# node.net
KiCad netlist of a schematic drawn in EAGLE
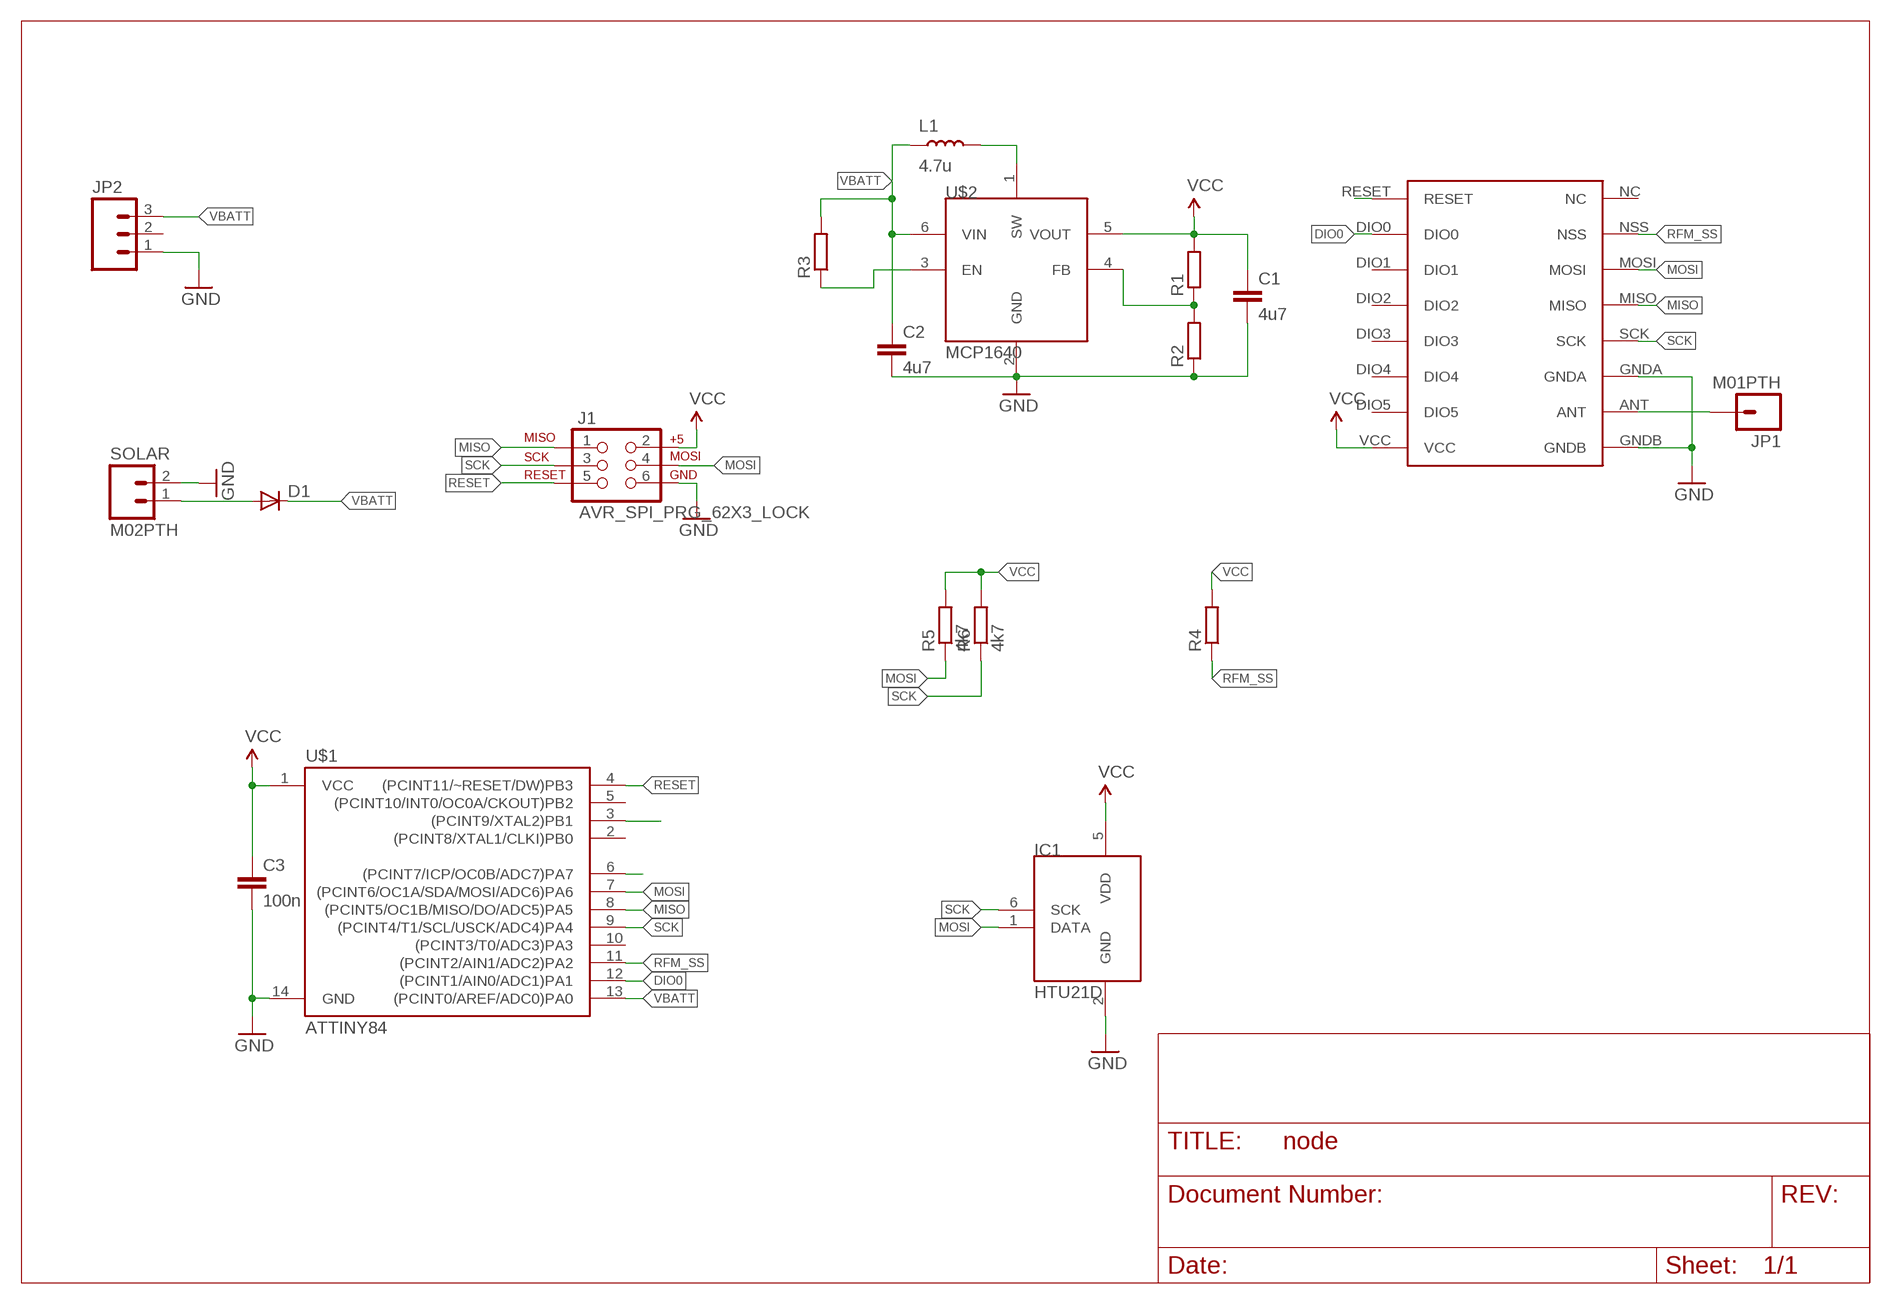
[diagram p0: schematic, sheet 1]

(export (version "E")
  (design (tool "Eeschema 10.0.6"))
  (components
    (comp (ref "C1")
      (value "4u7")
      (footprint "eagle-import:C0603")
      (libsource (lib "eagle-import") (part "C-EUC0603"))
    )
    (comp (ref "C2")
      (value "4u7")
      (footprint "eagle-import:C0603")
      (libsource (lib "eagle-import") (part "C-EUC0603"))
    )
    (comp (ref "C3")
      (value "100n")
      (footprint "eagle-import:C0603")
      (libsource (lib "eagle-import") (part "C-EUC0603"))
    )
    (comp (ref "D1")
      (value "DIODE-SOD123")
      (footprint "eagle-import:SOD123")
      (libsource (lib "eagle-import") (part "DIODE-SOD123"))
    )
    (comp (ref "IC1")
      (value "HTU21D")
      (footprint "eagle-import:DFN6-L")
      (libsource (lib "eagle-import") (part "HTU21D"))
    )
    (comp (ref "J1")
      (value "AVR_SPI_PRG_62X3_LOCK")
      (footprint "eagle-import:2X3_LOCK")
      (libsource (lib "eagle-import") (part "AVR_SPI_PRG_62X3_LOCK"))
    )
    (comp (ref "JP1")
      (value "M01PTH")
      (footprint "eagle-import:1X01")
      (libsource (lib "eagle-import") (part "M01PTH"))
    )
    (comp (ref "JP2")
      (value "M03PTH")
      (footprint "eagle-import:1X03")
      (libsource (lib "eagle-import") (part "M03PTH"))
    )
    (comp (ref "L1")
      (value "4.7u")
      (footprint "eagle-import:L0603-N")
      (libsource (lib "eagle-import") (part "INDUCTOR0603-N"))
    )
    (comp (ref "R1")
      (value "R-EU_R0603")
      (footprint "eagle-import:R0603")
      (libsource (lib "eagle-import") (part "R-EU_R0603"))
    )
    (comp (ref "R2")
      (value "R-EU_R0603")
      (footprint "eagle-import:R0603")
      (libsource (lib "eagle-import") (part "R-EU_R0603"))
    )
    (comp (ref "R3")
      (value "R-EU_R0603")
      (footprint "eagle-import:R0603")
      (libsource (lib "eagle-import") (part "R-EU_R0603"))
    )
    (comp (ref "R4")
      (value "R-EU_R0603")
      (footprint "eagle-import:R0603")
      (libsource (lib "eagle-import") (part "R-EU_R0603"))
    )
    (comp (ref "R5")
      (value "4k7")
      (footprint "eagle-import:R0603")
      (libsource (lib "eagle-import") (part "R-EU_R0603"))
    )
    (comp (ref "R6")
      (value "4k7")
      (footprint "eagle-import:R0603")
      (libsource (lib "eagle-import") (part "R-EU_R0603"))
    )
    (comp (ref "SOLAR")
      (value "M02PTH")
      (footprint "eagle-import:1X02")
      (libsource (lib "eagle-import") (part "M02PTH"))
    )
    (comp (ref "U$1")
      (value "ATTINY84")
      (footprint "eagle-import:SO14")
      (libsource (lib "eagle-import") (part "ATTINY84"))
    )
    (comp (ref "U$2")
      (value "MCP1640")
      (footprint "eagle-import:SOT23-6")
      (libsource (lib "eagle-import") (part "MCP1640"))
    )
    (comp (ref "U$4")
      (value "RFM69HW")
      (footprint "eagle-import:RFM")
      (libsource (lib "eagle-import") (part "RFM69HW"))
    )
  )
  (nets
    (net (code "1") (name "DIO0") (class "Default")
      (node (ref "U$1") (pin "12") (pinfunction "(PCINT1/AIN0/ADC1)PA1_12") (pintype "bidirectional"))
      (node (ref "U$4") (pin "DIO0") (pinfunction "DIO0_DIO0") (pintype "bidirectional"))
    )
    (net (code "2") (name "GND") (class "Default")
      (node (ref "C1") (pin "2") (pinfunction "2_2") (pintype "passive"))
      (node (ref "C2") (pin "2") (pinfunction "2_2") (pintype "passive"))
      (node (ref "C3") (pin "2") (pinfunction "2_2") (pintype "passive"))
      (node (ref "IC1") (pin "2") (pinfunction "GND_2") (pintype "power_in"))
      (node (ref "J1") (pin "6") (pinfunction "6_6") (pintype "passive"))
      (node (ref "JP2") (pin "1") (pinfunction "1_1") (pintype "passive"))
      (node (ref "R2") (pin "1") (pinfunction "1_1") (pintype "passive"))
      (node (ref "SOLAR") (pin "2") (pinfunction "2_2") (pintype "passive"))
      (node (ref "U$1") (pin "14") (pinfunction "GND_14") (pintype "bidirectional"))
      (node (ref "U$2") (pin "2") (pinfunction "GND_2") (pintype "power_in"))
      (node (ref "U$4") (pin "GNDA") (pinfunction "GNDA_GNDA") (pintype "bidirectional"))
      (node (ref "U$4") (pin "GNDB") (pinfunction "GNDB_GNDB") (pintype "bidirectional"))
    )
    (net (code "3") (name "MISO") (class "Default")
      (node (ref "J1") (pin "1") (pinfunction "1_1") (pintype "passive"))
      (node (ref "U$1") (pin "8") (pinfunction "(PCINT5/OC1B/MISO/DO/ADC5)PA5_8") (pintype "bidirectional"))
      (node (ref "U$4") (pin "MISO") (pinfunction "MISO_MISO") (pintype "bidirectional"))
    )
    (net (code "4") (name "MOSI") (class "Default")
      (node (ref "IC1") (pin "1") (pinfunction "DATA_1") (pintype "bidirectional"))
      (node (ref "J1") (pin "4") (pinfunction "4_4") (pintype "passive"))
      (node (ref "R5") (pin "1") (pinfunction "1_1") (pintype "passive"))
      (node (ref "U$1") (pin "7") (pinfunction "(PCINT6/OC1A/SDA/MOSI/ADC6)PA6_7") (pintype "bidirectional"))
      (node (ref "U$4") (pin "MOSI") (pinfunction "MOSI_MOSI") (pintype "bidirectional"))
    )
    (net (code "5") (name "Net-(D1-PadA)") (class "Default")
      (node (ref "D1") (pin "A") (pinfunction "A_A") (pintype "passive"))
      (node (ref "SOLAR") (pin "1") (pinfunction "1_1") (pintype "passive"))
    )
    (net (code "6") (name "Net-(JP1-Pad1)") (class "Default")
      (node (ref "JP1") (pin "1") (pinfunction "1_1") (pintype "passive"))
      (node (ref "U$4") (pin "ANT") (pinfunction "ANT_ANT") (pintype "bidirectional"))
    )
    (net (code "7") (name "Net-(L1-P$2)") (class "Default")
      (node (ref "L1") (pin "2") (pinfunction "P$2_2") (pintype "passive"))
      (node (ref "U$2") (pin "1") (pinfunction "SW_1") (pintype "input"))
    )
    (net (code "8") (name "Net-(U$2-EN)") (class "Default")
      (node (ref "R3") (pin "1") (pinfunction "1_1") (pintype "passive"))
      (node (ref "U$2") (pin "3") (pinfunction "EN_3") (pintype "input"))
    )
    (net (code "9") (name "Net-(U$2-FB)") (class "Default")
      (node (ref "R1") (pin "1") (pinfunction "1_1") (pintype "passive"))
      (node (ref "R2") (pin "2") (pinfunction "2_2") (pintype "passive"))
      (node (ref "U$2") (pin "4") (pinfunction "FB_4") (pintype "input"))
    )
    (net (code "10") (name "RESET") (class "Default")
      (node (ref "J1") (pin "5") (pinfunction "5_5") (pintype "passive"))
      (node (ref "U$1") (pin "4") (pinfunction "(PCINT11/~{RESET/DW})PB3_4") (pintype "bidirectional"))
    )
    (net (code "11") (name "RFM_SS") (class "Default")
      (node (ref "R4") (pin "1") (pinfunction "1_1") (pintype "passive"))
      (node (ref "U$1") (pin "11") (pinfunction "(PCINT2/AIN1/ADC2)PA2_11") (pintype "bidirectional"))
      (node (ref "U$4") (pin "NSS") (pinfunction "NSS_NSS") (pintype "bidirectional"))
    )
    (net (code "12") (name "SCK") (class "Default")
      (node (ref "IC1") (pin "6") (pinfunction "SCK_6") (pintype "input"))
      (node (ref "J1") (pin "3") (pinfunction "3_3") (pintype "passive"))
      (node (ref "R6") (pin "1") (pinfunction "1_1") (pintype "passive"))
      (node (ref "U$1") (pin "9") (pinfunction "(PCINT4/T1/SCL/USCK/ADC4)PA4_9") (pintype "bidirectional"))
      (node (ref "U$4") (pin "SCK") (pinfunction "SCK_SCK") (pintype "bidirectional"))
    )
    (net (code "13") (name "VBATT") (class "Default")
      (node (ref "C2") (pin "1") (pinfunction "1_1") (pintype "passive"))
      (node (ref "D1") (pin "C") (pinfunction "C_C") (pintype "passive"))
      (node (ref "JP2") (pin "3") (pinfunction "3_3") (pintype "passive"))
      (node (ref "L1") (pin "1") (pinfunction "P$1_1") (pintype "passive"))
      (node (ref "R3") (pin "2") (pinfunction "2_2") (pintype "passive"))
      (node (ref "U$1") (pin "13") (pinfunction "(PCINT0/AREF/ADC0)PA0_13") (pintype "bidirectional"))
      (node (ref "U$2") (pin "6") (pinfunction "VIN_6") (pintype "power_in"))
    )
    (net (code "14") (name "VCC") (class "Default")
      (node (ref "C1") (pin "1") (pinfunction "1_1") (pintype "passive"))
      (node (ref "C3") (pin "1") (pinfunction "1_1") (pintype "passive"))
      (node (ref "IC1") (pin "5") (pinfunction "VDD_5") (pintype "power_in"))
      (node (ref "J1") (pin "2") (pinfunction "2_2") (pintype "passive"))
      (node (ref "R1") (pin "2") (pinfunction "2_2") (pintype "passive"))
      (node (ref "R4") (pin "2") (pinfunction "2_2") (pintype "passive"))
      (node (ref "R5") (pin "2") (pinfunction "2_2") (pintype "passive"))
      (node (ref "R6") (pin "2") (pinfunction "2_2") (pintype "passive"))
      (node (ref "U$1") (pin "1") (pinfunction "VCC_1") (pintype "bidirectional"))
      (node (ref "U$2") (pin "5") (pinfunction "VOUT_5") (pintype "output"))
      (node (ref "U$4") (pin "VCC") (pinfunction "VCC_VCC") (pintype "bidirectional"))
    )
    (net (code "15") (name "unconnected-(JP2-Pad2)") (class "Default")
      (node (ref "JP2") (pin "2") (pinfunction "2_2") (pintype "passive"))
    )
    (net (code "16") (name "unconnected-(U$1-(PCINT3{slash}T0{slash}ADC3)PA3-Pad10)") (class "Default")
      (node (ref "U$1") (pin "10") (pinfunction "(PCINT3/T0/ADC3)PA3_10") (pintype "bidirectional"))
    )
    (net (code "17") (name "unconnected-(U$1-(PCINT7{slash}ICP{slash}OC0B{slash}ADC7)PA7-Pad6)") (class "Default")
      (node (ref "U$1") (pin "6") (pinfunction "(PCINT7/ICP/OC0B/ADC7)PA7_6") (pintype "bidirectional"))
    )
    (net (code "18") (name "unconnected-(U$1-(PCINT8{slash}XTAL1{slash}CLKI)PB0-Pad2)") (class "Default")
      (node (ref "U$1") (pin "2") (pinfunction "(PCINT8/XTAL1/CLKI)PB0_2") (pintype "bidirectional"))
    )
    (net (code "19") (name "unconnected-(U$1-(PCINT9{slash}XTAL2)PB1-Pad3)") (class "Default")
      (node (ref "U$1") (pin "3") (pinfunction "(PCINT9/XTAL2)PB1_3") (pintype "bidirectional"))
    )
    (net (code "20") (name "unconnected-(U$1-(PCINT10{slash}INT0{slash}OC0A{slash}CKOUT)PB2-Pad5)") (class "Default")
      (node (ref "U$1") (pin "5") (pinfunction "(PCINT10/INT0/OC0A/CKOUT)PB2_5") (pintype "bidirectional"))
    )
    (net (code "21") (name "unconnected-(U$4-PadDIO1)") (class "Default")
      (node (ref "U$4") (pin "DIO1") (pinfunction "DIO1_DIO1") (pintype "bidirectional"))
    )
    (net (code "22") (name "unconnected-(U$4-PadDIO2)") (class "Default")
      (node (ref "U$4") (pin "DIO2") (pinfunction "DIO2_DIO2") (pintype "bidirectional"))
    )
    (net (code "23") (name "unconnected-(U$4-PadDIO3)") (class "Default")
      (node (ref "U$4") (pin "DIO3") (pinfunction "DIO3_DIO3") (pintype "bidirectional"))
    )
    (net (code "24") (name "unconnected-(U$4-PadDIO4)") (class "Default")
      (node (ref "U$4") (pin "DIO4") (pinfunction "DIO4_DIO4") (pintype "bidirectional"))
    )
    (net (code "25") (name "unconnected-(U$4-PadDIO5)") (class "Default")
      (node (ref "U$4") (pin "DIO5") (pinfunction "DIO5_DIO5") (pintype "bidirectional"))
    )
    (net (code "26") (name "unconnected-(U$4-PadNC)") (class "Default")
      (node (ref "U$4") (pin "NC") (pinfunction "NC_NC") (pintype "bidirectional"))
    )
    (net (code "27") (name "unconnected-(U$4-PadRESET)") (class "Default")
      (node (ref "U$4") (pin "RESET") (pinfunction "RESET_RESET") (pintype "bidirectional"))
    )
  )
)
